# breeze_sensor.net
KiCad netlist of a schematic drawn in Altium Designer
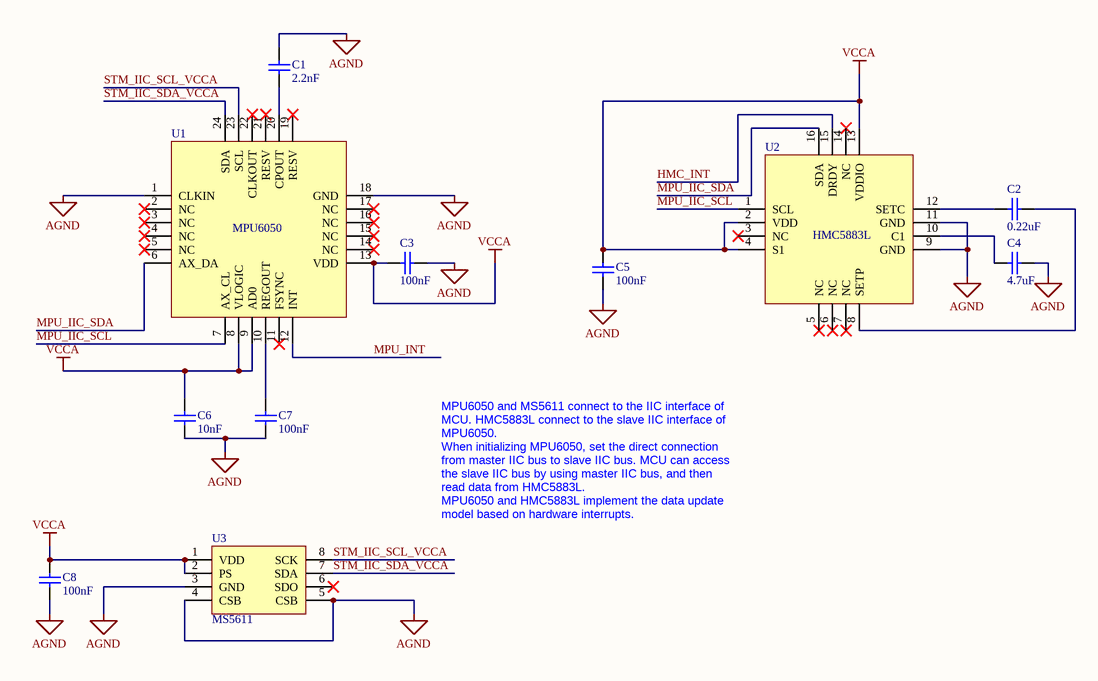
[diagram p0: breeze_sensor.SchDoc]

(export (version "E")
  (design (tool "Eeschema 10.0.6"))
  (components
    (comp (ref "C1")
      (value "2.2nF")
      (footprint "SMD-0603")
      (description "Capacitor")
      (fields (field (name "Comment") "CAP-0603"))
      (libsource (lib "breeze_design_library") (part "CAP-0603"))
    )
    (comp (ref "C2")
      (value "0.22uF")
      (footprint "SMD-0603")
      (description "Capacitor")
      (fields (field (name "Comment") "CAP-0603"))
      (libsource (lib "breeze_design_library") (part "CAP-0603"))
    )
    (comp (ref "C3")
      (value "100nF")
      (footprint "SMD-0603")
      (description "Capacitor")
      (fields (field (name "Comment") "CAP-0603"))
      (libsource (lib "breeze_design_library") (part "CAP-0603"))
    )
    (comp (ref "C4")
      (value "4.7uF")
      (footprint "SMD-0603")
      (description "Capacitor")
      (fields (field (name "Comment") "CAP-0603"))
      (libsource (lib "breeze_design_library") (part "CAP-0603"))
    )
    (comp (ref "C5")
      (value "100nF")
      (footprint "SMD-0603")
      (description "Capacitor")
      (fields (field (name "Comment") "CAP-0603"))
      (libsource (lib "breeze_design_library") (part "CAP-0603"))
    )
    (comp (ref "C6")
      (value "10nF")
      (footprint "SMD-0603")
      (description "Capacitor")
      (fields (field (name "Comment") "CAP-0603"))
      (libsource (lib "breeze_design_library") (part "CAP-0603"))
    )
    (comp (ref "C7")
      (value "100nF")
      (footprint "SMD-0603")
      (description "Capacitor")
      (fields (field (name "Comment") "CAP-0603"))
      (libsource (lib "breeze_design_library") (part "CAP-0603"))
    )
    (comp (ref "C8")
      (value "100nF")
      (footprint "SMD-0603")
      (description "Capacitor")
      (fields (field (name "Comment") "CAP-0603"))
      (libsource (lib "breeze_design_library") (part "CAP-0603"))
    )
    (comp (ref "U1")
      (value "MPU6050")
      (footprint "QFN-24")
      (description "6-axis Motion Tracking IC")
      (libsource (lib "breeze_design_library") (part "MPU6050"))
    )
    (comp (ref "U2")
      (value "HMC5883L")
      (footprint "LPCC-16")
      (description "3-Axis Digital Compass IC")
      (libsource (lib "breeze_design_library") (part "HMC5883L"))
    )
    (comp (ref "U3")
      (value "MS5611")
      (footprint "MS5611")
      (description "High Resolution Altimeter IC")
      (libsource (lib "breeze_design_library") (part "MS5611"))
    )
  )
  (nets
    (net (code "1") (name "/HMC_INT") (class "Default")
      (node (ref "U2") (pin "15") (pinfunction "DRDY_15") (pintype "passive"))
    )
    (net (code "2") (name "/MPU_IIC_SCL") (class "Default")
      (node (ref "U1") (pin "7") (pinfunction "AX_CL_7") (pintype "passive"))
      (node (ref "U2") (pin "1") (pinfunction "SCL_1") (pintype "passive"))
    )
    (net (code "3") (name "/MPU_IIC_SDA") (class "Default")
      (node (ref "U1") (pin "6") (pinfunction "AX_DA_6") (pintype "passive"))
      (node (ref "U2") (pin "16") (pinfunction "SDA_16") (pintype "passive"))
    )
    (net (code "4") (name "/MPU_INT") (class "Default")
      (node (ref "U1") (pin "12") (pinfunction "INT_12") (pintype "passive"))
    )
    (net (code "5") (name "/STM_IIC_SCL_VCCA") (class "Default")
      (node (ref "U1") (pin "23") (pinfunction "SCL_23") (pintype "passive"))
      (node (ref "U3") (pin "8") (pinfunction "SCK_8") (pintype "passive"))
    )
    (net (code "6") (name "/STM_IIC_SDA_VCCA") (class "Default")
      (node (ref "U1") (pin "24") (pinfunction "SDA_24") (pintype "passive"))
      (node (ref "U3") (pin "7") (pinfunction "SDA_7") (pintype "passive"))
    )
    (net (code "7") (name "AGND") (class "Default")
      (node (ref "C1") (pin "2") (pinfunction "2_2") (pintype "passive"))
      (node (ref "C3") (pin "2") (pinfunction "2_2") (pintype "passive"))
      (node (ref "C4") (pin "2") (pinfunction "2_2") (pintype "passive"))
      (node (ref "C5") (pin "2") (pinfunction "2_2") (pintype "passive"))
      (node (ref "C6") (pin "2") (pinfunction "2_2") (pintype "passive"))
      (node (ref "C7") (pin "2") (pinfunction "2_2") (pintype "passive"))
      (node (ref "C8") (pin "2") (pinfunction "2_2") (pintype "passive"))
      (node (ref "U1") (pin "1") (pinfunction "CLKIN_1") (pintype "passive"))
      (node (ref "U1") (pin "18") (pinfunction "GND_18") (pintype "passive"))
      (node (ref "U2") (pin "11") (pinfunction "GND_11") (pintype "passive"))
      (node (ref "U2") (pin "9") (pinfunction "GND_9") (pintype "passive"))
      (node (ref "U3") (pin "3") (pinfunction "GND_3") (pintype "passive"))
      (node (ref "U3") (pin "4") (pinfunction "CSB_4") (pintype "passive"))
      (node (ref "U3") (pin "5") (pinfunction "CSB_5") (pintype "passive"))
    )
    (net (code "8") (name "Net-(U1-CPOUT)") (class "Default")
      (node (ref "C1") (pin "1") (pinfunction "1_1") (pintype "passive"))
      (node (ref "U1") (pin "20") (pinfunction "CPOUT_20") (pintype "passive"))
    )
    (net (code "9") (name "Net-(U1-REGOUT)") (class "Default")
      (node (ref "C7") (pin "1") (pinfunction "1_1") (pintype "passive"))
      (node (ref "U1") (pin "10") (pinfunction "REGOUT_10") (pintype "passive"))
    )
    (net (code "10") (name "Net-(U2-C1)") (class "Default")
      (node (ref "C4") (pin "1") (pinfunction "1_1") (pintype "passive"))
      (node (ref "U2") (pin "10") (pinfunction "C1_10") (pintype "passive"))
    )
    (net (code "11") (name "Net-(U2-SETC)") (class "Default")
      (node (ref "C2") (pin "1") (pinfunction "1_1") (pintype "passive"))
      (node (ref "U2") (pin "12") (pinfunction "SETC_12") (pintype "passive"))
    )
    (net (code "12") (name "Net-(U2-SETP)") (class "Default")
      (node (ref "C2") (pin "2") (pinfunction "2_2") (pintype "passive"))
      (node (ref "U2") (pin "8") (pinfunction "SETP_8") (pintype "passive"))
    )
    (net (code "13") (name "VCCA") (class "Default")
      (node (ref "C3") (pin "1") (pinfunction "1_1") (pintype "passive"))
      (node (ref "C5") (pin "1") (pinfunction "1_1") (pintype "passive"))
      (node (ref "C6") (pin "1") (pinfunction "1_1") (pintype "passive"))
      (node (ref "C8") (pin "1") (pinfunction "1_1") (pintype "passive"))
      (node (ref "U1") (pin "13") (pinfunction "VDD_13") (pintype "passive"))
      (node (ref "U1") (pin "8") (pinfunction "VLOGIC_8") (pintype "passive"))
      (node (ref "U1") (pin "9") (pinfunction "AD0_9") (pintype "passive"))
      (node (ref "U2") (pin "13") (pinfunction "VDDIO_13") (pintype "passive"))
      (node (ref "U2") (pin "2") (pinfunction "VDD_2") (pintype "passive"))
      (node (ref "U2") (pin "4") (pinfunction "S1_4") (pintype "passive"))
      (node (ref "U3") (pin "1") (pinfunction "VDD_1") (pintype "passive"))
      (node (ref "U3") (pin "2") (pinfunction "PS_2") (pintype "passive"))
    )
    (net (code "14") (name "unconnected-(U1-CLKOUT-Pad22)") (class "Default")
      (node (ref "U1") (pin "22") (pinfunction "CLKOUT_22") (pintype "passive+no_connect"))
    )
    (net (code "15") (name "unconnected-(U1-FSYNC-Pad11)") (class "Default")
      (node (ref "U1") (pin "11") (pinfunction "FSYNC_11") (pintype "passive+no_connect"))
    )
    (net (code "16") (name "unconnected-(U1-NC-Pad2)") (class "Default")
      (node (ref "U1") (pin "2") (pinfunction "NC_2") (pintype "passive+no_connect"))
    )
    (net (code "17") (name "unconnected-(U1-NC-Pad3)") (class "Default")
      (node (ref "U1") (pin "3") (pinfunction "NC_3") (pintype "passive+no_connect"))
    )
    (net (code "18") (name "unconnected-(U1-NC-Pad4)") (class "Default")
      (node (ref "U1") (pin "4") (pinfunction "NC_4") (pintype "passive+no_connect"))
    )
    (net (code "19") (name "unconnected-(U1-NC-Pad5)") (class "Default")
      (node (ref "U1") (pin "5") (pinfunction "NC_5") (pintype "passive+no_connect"))
    )
    (net (code "20") (name "unconnected-(U1-NC-Pad14)") (class "Default")
      (node (ref "U1") (pin "14") (pinfunction "NC_14") (pintype "passive+no_connect"))
    )
    (net (code "21") (name "unconnected-(U1-NC-Pad15)") (class "Default")
      (node (ref "U1") (pin "15") (pinfunction "NC_15") (pintype "passive+no_connect"))
    )
    (net (code "22") (name "unconnected-(U1-NC-Pad16)") (class "Default")
      (node (ref "U1") (pin "16") (pinfunction "NC_16") (pintype "passive+no_connect"))
    )
    (net (code "23") (name "unconnected-(U1-NC-Pad17)") (class "Default")
      (node (ref "U1") (pin "17") (pinfunction "NC_17") (pintype "passive+no_connect"))
    )
    (net (code "24") (name "unconnected-(U1-RESV-Pad19)") (class "Default")
      (node (ref "U1") (pin "19") (pinfunction "RESV_19") (pintype "passive+no_connect"))
    )
    (net (code "25") (name "unconnected-(U1-RESV-Pad21)") (class "Default")
      (node (ref "U1") (pin "21") (pinfunction "RESV_21") (pintype "passive+no_connect"))
    )
    (net (code "26") (name "unconnected-(U2-NC-Pad3)") (class "Default")
      (node (ref "U2") (pin "3") (pinfunction "NC_3") (pintype "passive+no_connect"))
    )
    (net (code "27") (name "unconnected-(U2-NC-Pad5)") (class "Default")
      (node (ref "U2") (pin "5") (pinfunction "NC_5") (pintype "passive+no_connect"))
    )
    (net (code "28") (name "unconnected-(U2-NC-Pad6)") (class "Default")
      (node (ref "U2") (pin "6") (pinfunction "NC_6") (pintype "passive+no_connect"))
    )
    (net (code "29") (name "unconnected-(U2-NC-Pad7)") (class "Default")
      (node (ref "U2") (pin "7") (pinfunction "NC_7") (pintype "passive+no_connect"))
    )
    (net (code "30") (name "unconnected-(U2-NC-Pad14)") (class "Default")
      (node (ref "U2") (pin "14") (pinfunction "NC_14") (pintype "passive+no_connect"))
    )
    (net (code "31") (name "unconnected-(U3-SDO-Pad6)") (class "Default")
      (node (ref "U3") (pin "6") (pinfunction "SDO_6") (pintype "passive+no_connect"))
    )
  )
)
